# SoC_Peripheral.net
KiCad netlist of a schematic drawn in Altium Designer
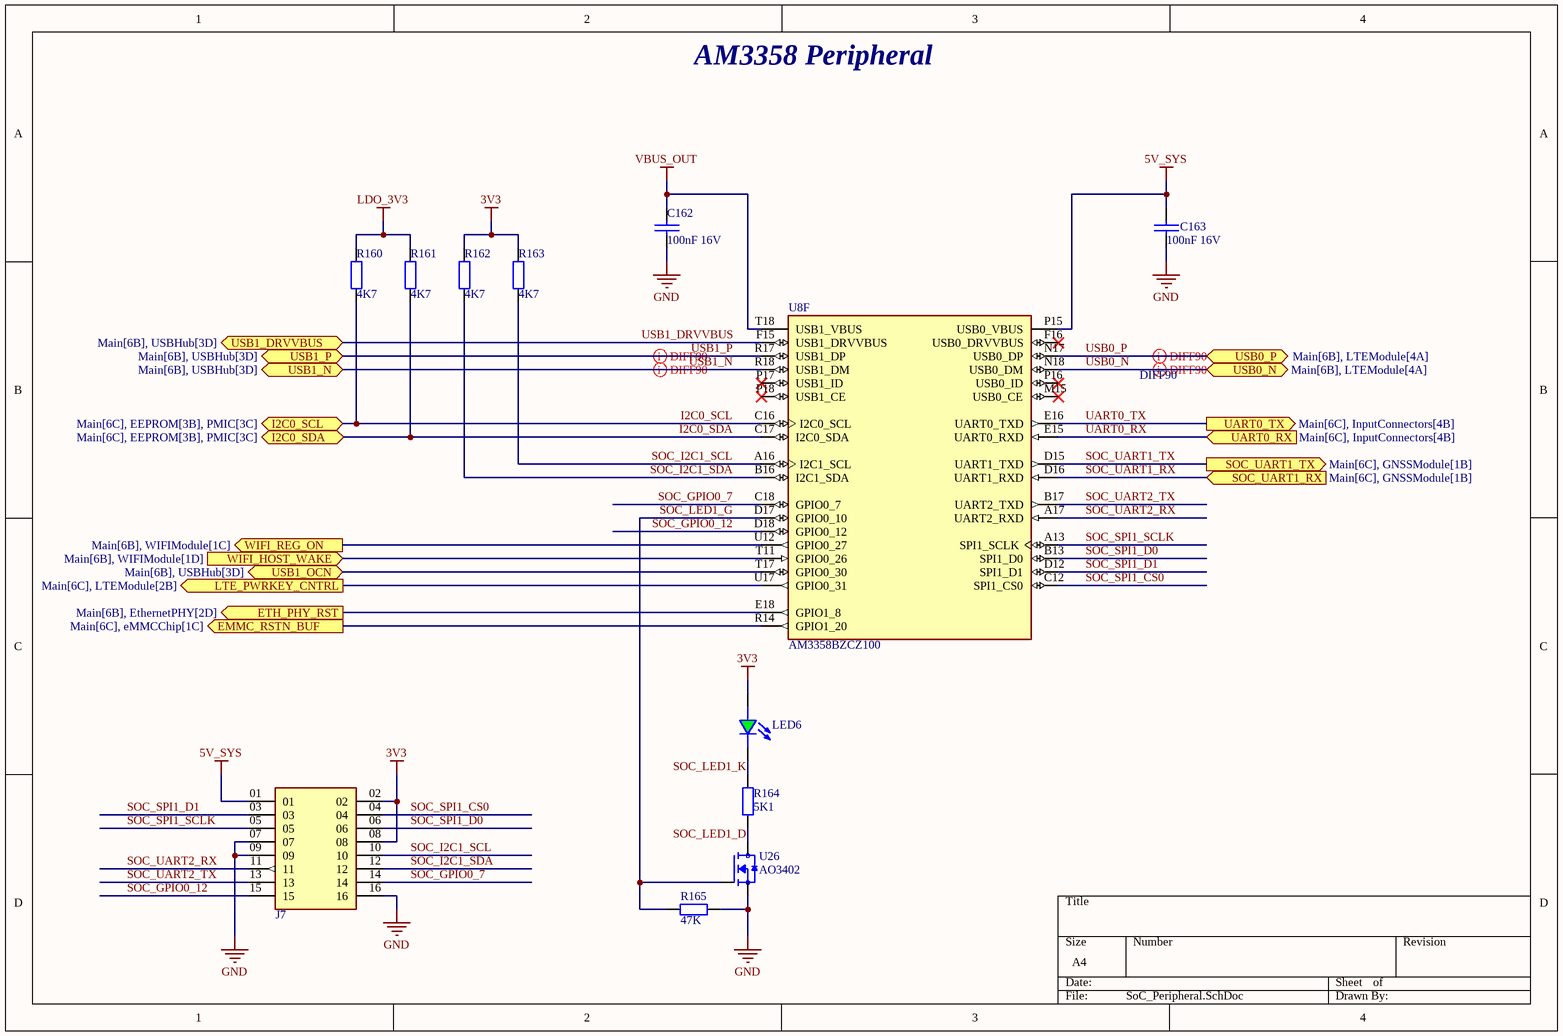
[diagram p0: SoC_Peripheral.SchDoc]

(export (version "E")
  (design (tool "Eeschema 10.0.6"))
  (components
    (comp (ref "C162")
      (value "100nF 16V")
      (footprint "C_0402")
      (description "Capacitor 0402 SMD")
      (libsource (lib "tor1kkLib") (part "C_0402"))
    )
    (comp (ref "C163")
      (value "100nF 16V")
      (footprint "C_0402")
      (description "Capacitor 0402 SMD")
      (libsource (lib "tor1kkLib") (part "C_0402"))
    )
    (comp (ref "J7")
      (value "header_2.54_16pin_2row")
      (footprint "header_2.54_16pin_2row")
      (libsource (lib "tor1kkLib") (part "header_2.54_16pin_2row"))
    )
    (comp (ref "LED6")
      (value "LED_0603_GREEN")
      (footprint "LED_0603")
      (libsource (lib "tor1kkLib") (part "LED_0603_GREEN"))
    )
    (comp (ref "R160")
      (value "4K7")
      (footprint "R_0402")
      (description "Resistor 0402 SMD")
      (libsource (lib "tor1kkLib") (part "R_0402"))
    )
    (comp (ref "R161")
      (value "4K7")
      (footprint "R_0402")
      (description "Resistor 0402 SMD")
      (libsource (lib "tor1kkLib") (part "R_0402"))
    )
    (comp (ref "R162")
      (value "4K7")
      (footprint "R_0402")
      (description "Resistor 0402 SMD")
      (libsource (lib "tor1kkLib") (part "R_0402"))
    )
    (comp (ref "R163")
      (value "4K7")
      (footprint "R_0402")
      (description "Resistor 0402 SMD")
      (libsource (lib "tor1kkLib") (part "R_0402"))
    )
    (comp (ref "R164")
      (value "5K1")
      (footprint "R_0603")
      (description "Resistor 0603 SMD")
      (libsource (lib "") (part "R_0603_1"))
    )
    (comp (ref "R165")
      (value "47K")
      (footprint "R_0603")
      (description "Resistor 0603 SMD")
      (libsource (lib "tor1kkLib") (part "R_0603"))
    )
    (comp (ref "U8")
      (value "AM3358BZCZ100")
      (footprint "BGA324C80P18X18_1500X1500X140")
      (description "ARM-ASeries 1GHz NFBGA-324 Microcontrollers (MCU/MPU/SOC) ROHS")
      (fields (field (name "MANUFACTURER") "Texas Instruments"))
      (libsource (lib "tor1kkLib") (part "AM3358BZCZ100"))
    )
    (comp (ref "U26")
      (value "AO3402")
      (footprint "SOT-23-3")
      (description "N-Channel 30 V 4A (Ta) 1.4W (Ta) Surface Mount SOT-23-3")
      (fields (field (name "MANUFACTURER") "Alpha & Omega Semicon"))
      (libsource (lib "tor1kkLib") (part "AO3402"))
    )
  )
  (nets
    (net (code "1") (name "/EMMC_RSTN_BUF") (class "Default")
      (node (ref "U8") (pin "R14") (pinfunction "GPIO1_20_R14") (pintype "output"))
    )
    (net (code "2") (name "/ETH_PHY_RST") (class "Default")
      (node (ref "U8") (pin "E18") (pinfunction "GPIO1_8_E18") (pintype "output"))
    )
    (net (code "3") (name "/I2C0_SCL") (class "Default")
      (node (ref "R160") (pin "1") (pintype "passive"))
      (node (ref "U8") (pin "C16") (pinfunction "I2C0_SCL_C16") (pintype "bidirectional"))
    )
    (net (code "4") (name "/I2C0_SDA") (class "Default")
      (node (ref "R161") (pin "1") (pintype "passive"))
      (node (ref "U8") (pin "C17") (pinfunction "I2C0_SDA_C17") (pintype "bidirectional"))
    )
    (net (code "5") (name "/LTE_PWRKEY_CNTRL") (class "Default")
      (node (ref "U8") (pin "U17") (pinfunction "GPIO0_31_U17") (pintype "output"))
    )
    (net (code "6") (name "/SOC_GPIO0_7") (class "Default")
      (node (ref "J7") (pin "14") (pinfunction "14_14") (pintype "passive"))
      (node (ref "U8") (pin "C18") (pinfunction "GPIO0_7_C18") (pintype "bidirectional"))
    )
    (net (code "7") (name "/SOC_GPIO0_12") (class "Default")
      (node (ref "J7") (pin "15") (pinfunction "15_15") (pintype "passive"))
      (node (ref "U8") (pin "D18") (pinfunction "GPIO0_12_D18") (pintype "bidirectional"))
    )
    (net (code "8") (name "/SOC_I2C1_SCL") (class "Default")
      (node (ref "J7") (pin "10") (pinfunction "10_10") (pintype "passive"))
      (node (ref "R163") (pin "1") (pintype "passive"))
      (node (ref "U8") (pin "A16") (pinfunction "I2C1_SCL_A16") (pintype "bidirectional"))
    )
    (net (code "9") (name "/SOC_I2C1_SDA") (class "Default")
      (node (ref "J7") (pin "12") (pinfunction "12_12") (pintype "passive"))
      (node (ref "R162") (pin "1") (pintype "passive"))
      (node (ref "U8") (pin "B16") (pinfunction "I2C1_SDA_B16") (pintype "bidirectional"))
    )
    (net (code "10") (name "/SOC_LED1_D") (class "Default")
      (node (ref "R164") (pin "1") (pintype "passive"))
      (node (ref "U26") (pin "3") (pinfunction "D_3") (pintype "passive"))
    )
    (net (code "11") (name "/SOC_LED1_G") (class "Default")
      (node (ref "R165") (pin "1") (pintype "passive"))
      (node (ref "U26") (pin "1") (pinfunction "G_1") (pintype "passive"))
      (node (ref "U8") (pin "D17") (pinfunction "GPIO0_10_D17") (pintype "bidirectional"))
    )
    (net (code "12") (name "/SOC_LED1_K") (class "Default")
      (node (ref "LED6") (pin "2") (pinfunction "C_2") (pintype "passive"))
      (node (ref "R164") (pin "2") (pintype "passive"))
    )
    (net (code "13") (name "/SOC_SPI1_CS0") (class "Default")
      (node (ref "J7") (pin "04") (pinfunction "04_04") (pintype "passive"))
      (node (ref "U8") (pin "C12") (pinfunction "SPI1_CS0_C12") (pintype "bidirectional"))
    )
    (net (code "14") (name "/SOC_SPI1_D0") (class "Default")
      (node (ref "J7") (pin "06") (pinfunction "06_06") (pintype "passive"))
      (node (ref "U8") (pin "B13") (pinfunction "SPI1_D0_B13") (pintype "bidirectional"))
    )
    (net (code "15") (name "/SOC_SPI1_D1") (class "Default")
      (node (ref "J7") (pin "03") (pinfunction "03_03") (pintype "passive"))
      (node (ref "U8") (pin "D12") (pinfunction "SPI1_D1_D12") (pintype "bidirectional"))
    )
    (net (code "16") (name "/SOC_SPI1_SCLK") (class "Default")
      (node (ref "J7") (pin "05") (pinfunction "05_05") (pintype "passive"))
      (node (ref "U8") (pin "A13") (pinfunction "SPI1_SCLK_A13") (pintype "bidirectional"))
    )
    (net (code "17") (name "/SOC_UART1_RX") (class "Default")
      (node (ref "U8") (pin "D16") (pinfunction "UART1_RXD_D16") (pintype "input"))
    )
    (net (code "18") (name "/SOC_UART1_TX") (class "Default")
      (node (ref "U8") (pin "D15") (pinfunction "UART1_TXD_D15") (pintype "output"))
    )
    (net (code "19") (name "/SOC_UART2_RX") (class "Default")
      (node (ref "J7") (pin "11") (pinfunction "11_11") (pintype "output"))
      (node (ref "U8") (pin "A17") (pinfunction "UART2_RXD_A17") (pintype "input"))
    )
    (net (code "20") (name "/SOC_UART2_TX") (class "Default")
      (node (ref "J7") (pin "13") (pinfunction "13_13") (pintype "passive"))
      (node (ref "U8") (pin "B17") (pinfunction "UART2_TXD_B17") (pintype "output"))
    )
    (net (code "21") (name "/UART0_RX") (class "Default")
      (node (ref "U8") (pin "E15") (pinfunction "UART0_RXD_E15") (pintype "input"))
    )
    (net (code "22") (name "/UART0_TX") (class "Default")
      (node (ref "U8") (pin "E16") (pinfunction "UART0_TXD_E16") (pintype "output"))
    )
    (net (code "23") (name "/USB0_N") (class "Default")
      (node (ref "U8") (pin "N18") (pinfunction "USB0_DM_N18") (pintype "bidirectional"))
    )
    (net (code "24") (name "/USB0_P") (class "Default")
      (node (ref "U8") (pin "N17") (pinfunction "USB0_DP_N17") (pintype "bidirectional"))
    )
    (net (code "25") (name "/USB1_DRVVBUS") (class "Default")
      (node (ref "U8") (pin "F15") (pinfunction "USB1_DRVVBUS_F15") (pintype "bidirectional"))
    )
    (net (code "26") (name "/USB1_N") (class "Default")
      (node (ref "U8") (pin "R18") (pinfunction "USB1_DM_R18") (pintype "bidirectional"))
    )
    (net (code "27") (name "/USB1_OCN") (class "Default")
      (node (ref "U8") (pin "T17") (pinfunction "GPIO0_30_T17") (pintype "bidirectional"))
    )
    (net (code "28") (name "/USB1_P") (class "Default")
      (node (ref "U8") (pin "R17") (pinfunction "USB1_DP_R17") (pintype "bidirectional"))
    )
    (net (code "29") (name "/WIFI_HOST_WAKE") (class "Default")
      (node (ref "U8") (pin "T11") (pinfunction "GPIO0_26_T11") (pintype "input"))
    )
    (net (code "30") (name "/WIFI_REG_ON") (class "Default")
      (node (ref "U8") (pin "U12") (pinfunction "GPIO0_27_U12") (pintype "output"))
    )
    (net (code "31") (name "3V3") (class "Default")
      (node (ref "J7") (pin "02") (pinfunction "02_02") (pintype "passive"))
      (node (ref "J7") (pin "08") (pinfunction "08_08") (pintype "passive"))
      (node (ref "LED6") (pin "1") (pinfunction "A_1") (pintype "passive"))
      (node (ref "R162") (pin "2") (pintype "passive"))
      (node (ref "R163") (pin "2") (pintype "passive"))
    )
    (net (code "32") (name "5V_SYS") (class "Default")
      (node (ref "C163") (pin "1") (pintype "passive"))
      (node (ref "J7") (pin "01") (pinfunction "01_01") (pintype "passive"))
      (node (ref "U8") (pin "P15") (pinfunction "USB0_VBUS_P15") (pintype "passive"))
    )
    (net (code "33") (name "GND") (class "Default")
      (node (ref "C162") (pin "2") (pintype "passive"))
      (node (ref "C163") (pin "2") (pintype "passive"))
      (node (ref "J7") (pin "07") (pinfunction "07_07") (pintype "passive"))
      (node (ref "J7") (pin "09") (pinfunction "09_09") (pintype "passive"))
      (node (ref "J7") (pin "16") (pinfunction "16_16") (pintype "passive"))
      (node (ref "R165") (pin "2") (pintype "passive"))
      (node (ref "U26") (pin "2") (pinfunction "S_2") (pintype "passive"))
    )
    (net (code "34") (name "LDO_3V3") (class "Default")
      (node (ref "R160") (pin "2") (pintype "passive"))
      (node (ref "R161") (pin "2") (pintype "passive"))
    )
    (net (code "35") (name "VBUS_OUT") (class "Default")
      (node (ref "C162") (pin "1") (pintype "passive"))
      (node (ref "U8") (pin "T18") (pinfunction "USB1_VBUS_T18") (pintype "passive"))
    )
    (net (code "36") (name "unconnected-(U8F-USB0_CE-PadM15)") (class "Default")
      (node (ref "U8") (pin "M15") (pinfunction "USB0_CE_M15") (pintype "bidirectional+no_connect"))
    )
    (net (code "37") (name "unconnected-(U8F-USB0_DRVVBUS-PadF16)") (class "Default")
      (node (ref "U8") (pin "F16") (pinfunction "USB0_DRVVBUS_F16") (pintype "bidirectional+no_connect"))
    )
    (net (code "38") (name "unconnected-(U8F-USB0_ID-PadP16)") (class "Default")
      (node (ref "U8") (pin "P16") (pinfunction "USB0_ID_P16") (pintype "bidirectional+no_connect"))
    )
    (net (code "39") (name "unconnected-(U8F-USB1_CE-PadP18)") (class "Default")
      (node (ref "U8") (pin "P18") (pinfunction "USB1_CE_P18") (pintype "bidirectional+no_connect"))
    )
    (net (code "40") (name "unconnected-(U8F-USB1_ID-PadP17)") (class "Default")
      (node (ref "U8") (pin "P17") (pinfunction "USB1_ID_P17") (pintype "bidirectional+no_connect"))
    )
  )
)
